# usb_snes_v2.net
KiCad netlist of a schematic drawn in EAGLE
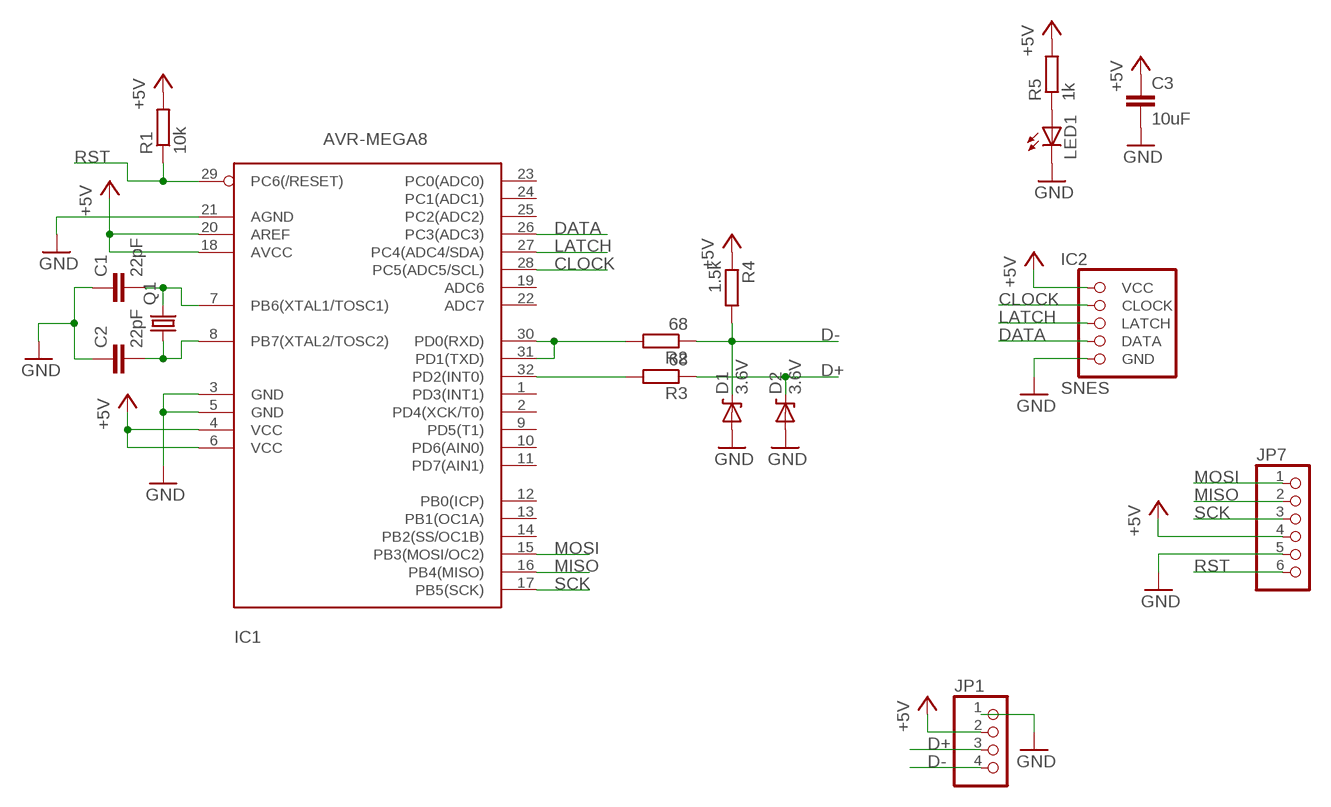
[diagram p0: schematic, sheet 1]

(export (version "E")
  (design (tool "Eeschema 10.0.6"))
  (components
    (comp (ref "C1")
      (value "22pF")
      (footprint "eagle-import:R0805")
      (libsource (lib "eagle-import") (part "C-EUR0805"))
    )
    (comp (ref "C2")
      (value "22pF")
      (footprint "eagle-import:R0805")
      (libsource (lib "eagle-import") (part "C-EUR0805"))
    )
    (comp (ref "C3")
      (value "10uF")
      (footprint "eagle-import:R0805")
      (libsource (lib "eagle-import") (part "C-EUR0805"))
    )
    (comp (ref "D1")
      (value "3.6V")
      (footprint "eagle-import:SOD123FL")
      (libsource (lib "eagle-import") (part "DIODE-ZENERFL"))
    )
    (comp (ref "D2")
      (value "3.6V")
      (footprint "eagle-import:SOD123FL")
      (libsource (lib "eagle-import") (part "DIODE-ZENERFL"))
    )
    (comp (ref "IC1")
      (value "AVR-MEGA8")
      (footprint "eagle-import:TQFP32-08")
      (libsource (lib "eagle-import") (part "AVR-MEGA8-AI"))
    )
    (comp (ref "IC2")
      (value "SNES")
      (footprint "eagle-import:SNES")
      (libsource (lib "eagle-import") (part "SNES"))
    )
    (comp (ref "JP1")
      (value "PINHD-1X4S")
      (footprint "eagle-import:1X04-2MM")
      (libsource (lib "eagle-import") (part "PINHD-1X4S"))
    )
    (comp (ref "JP7")
      (value "PINHD-1X6S")
      (footprint "eagle-import:1X06-2MM")
      (libsource (lib "eagle-import") (part "PINHD-1X6S"))
    )
    (comp (ref "LED1")
      (value "LED0805")
      (footprint "eagle-import:CHIP-LED0805")
      (libsource (lib "eagle-import") (part "LED0805"))
    )
    (comp (ref "Q1")
      (value "CRYSTALHC49UP")
      (footprint "eagle-import:HC49UP")
      (libsource (lib "eagle-import") (part "CRYSTALHC49UP"))
    )
    (comp (ref "R1")
      (value "10k")
      (footprint "eagle-import:R0805")
      (libsource (lib "eagle-import") (part "R-EU_R0805"))
    )
    (comp (ref "R2")
      (value "68")
      (footprint "eagle-import:R0805")
      (libsource (lib "eagle-import") (part "R-EU_R0805"))
    )
    (comp (ref "R3")
      (value "68")
      (footprint "eagle-import:R0805")
      (libsource (lib "eagle-import") (part "R-EU_R0805"))
    )
    (comp (ref "R4")
      (value "1.5k")
      (footprint "eagle-import:R0805")
      (libsource (lib "eagle-import") (part "R-EU_R0805"))
    )
    (comp (ref "R5")
      (value "1k")
      (footprint "eagle-import:R0805")
      (libsource (lib "eagle-import") (part "R-EU_R0805"))
    )
  )
  (nets
    (net (code "1") (name "+5V") (class "Default")
      (node (ref "C3") (pin "1") (pinfunction "1_1") (pintype "passive"))
      (node (ref "IC1") (pin "18") (pinfunction "AVCC_18") (pintype "bidirectional"))
      (node (ref "IC1") (pin "20") (pinfunction "AREF_20") (pintype "bidirectional"))
      (node (ref "IC1") (pin "4") (pinfunction "VCC_4") (pintype "bidirectional"))
      (node (ref "IC1") (pin "6") (pinfunction "VCC_6") (pintype "bidirectional"))
      (node (ref "IC2") (pin "5") (pinfunction "VCC_5") (pintype "passive"))
      (node (ref "JP1") (pin "2") (pinfunction "2_2") (pintype "passive"))
      (node (ref "JP7") (pin "4") (pinfunction "4_4") (pintype "passive"))
      (node (ref "R1") (pin "2") (pinfunction "2_2") (pintype "passive"))
      (node (ref "R4") (pin "1") (pinfunction "1_1") (pintype "passive"))
      (node (ref "R5") (pin "2") (pinfunction "2_2") (pintype "passive"))
    )
    (net (code "2") (name "/CLOCK") (class "Default")
      (node (ref "IC1") (pin "28") (pinfunction "PC5(ADC5/SCL)_28") (pintype "bidirectional"))
      (node (ref "IC2") (pin "4") (pinfunction "CLOCK_4") (pintype "passive"))
    )
    (net (code "3") (name "/D+") (class "Default")
      (node (ref "D2") (pin "C") (pinfunction "C_C") (pintype "passive"))
      (node (ref "JP1") (pin "3") (pinfunction "3_3") (pintype "passive"))
      (node (ref "R3") (pin "1") (pinfunction "1_1") (pintype "passive"))
    )
    (net (code "4") (name "/D-") (class "Default")
      (node (ref "D1") (pin "C") (pinfunction "C_C") (pintype "passive"))
      (node (ref "JP1") (pin "4") (pinfunction "4_4") (pintype "passive"))
      (node (ref "R2") (pin "1") (pinfunction "1_1") (pintype "passive"))
      (node (ref "R4") (pin "2") (pinfunction "2_2") (pintype "passive"))
    )
    (net (code "5") (name "/DATA") (class "Default")
      (node (ref "IC1") (pin "26") (pinfunction "PC3(ADC3)_26") (pintype "bidirectional"))
      (node (ref "IC2") (pin "2") (pinfunction "DATA_2") (pintype "passive"))
    )
    (net (code "6") (name "/LATCH") (class "Default")
      (node (ref "IC1") (pin "27") (pinfunction "PC4(ADC4/SDA)_27") (pintype "bidirectional"))
      (node (ref "IC2") (pin "3") (pinfunction "LATCH_3") (pintype "passive"))
    )
    (net (code "7") (name "/MISO") (class "Default")
      (node (ref "IC1") (pin "16") (pinfunction "PB4(MISO)_16") (pintype "bidirectional"))
      (node (ref "JP7") (pin "2") (pinfunction "2_2") (pintype "passive"))
    )
    (net (code "8") (name "/MOSI") (class "Default")
      (node (ref "IC1") (pin "15") (pinfunction "PB3(MOSI/OC2)_15") (pintype "bidirectional"))
      (node (ref "JP7") (pin "1") (pinfunction "1_1") (pintype "passive"))
    )
    (net (code "9") (name "/RST") (class "Default")
      (node (ref "IC1") (pin "29") (pinfunction "PC6(/RESET)_29") (pintype "bidirectional"))
      (node (ref "JP7") (pin "6") (pinfunction "6_6") (pintype "passive"))
      (node (ref "R1") (pin "1") (pinfunction "1_1") (pintype "passive"))
    )
    (net (code "10") (name "/SCK") (class "Default")
      (node (ref "IC1") (pin "17") (pinfunction "PB5(SCK)_17") (pintype "bidirectional"))
      (node (ref "JP7") (pin "3") (pinfunction "3_3") (pintype "passive"))
    )
    (net (code "11") (name "GND") (class "Default")
      (node (ref "C1") (pin "1") (pinfunction "1_1") (pintype "passive"))
      (node (ref "C2") (pin "1") (pinfunction "1_1") (pintype "passive"))
      (node (ref "C3") (pin "2") (pinfunction "2_2") (pintype "passive"))
      (node (ref "D1") (pin "A") (pinfunction "A_A") (pintype "passive"))
      (node (ref "D2") (pin "A") (pinfunction "A_A") (pintype "passive"))
      (node (ref "IC1") (pin "21") (pinfunction "AGND_21") (pintype "bidirectional"))
      (node (ref "IC1") (pin "3") (pinfunction "GND_3") (pintype "bidirectional"))
      (node (ref "IC1") (pin "5") (pinfunction "GND_5") (pintype "bidirectional"))
      (node (ref "IC2") (pin "1") (pinfunction "GND_1") (pintype "passive"))
      (node (ref "JP1") (pin "1") (pinfunction "1_1") (pintype "passive"))
      (node (ref "JP7") (pin "5") (pinfunction "5_5") (pintype "passive"))
      (node (ref "LED1") (pin "C") (pinfunction "C_C") (pintype "passive"))
    )
    (net (code "12") (name "Net-(IC1-PB6(XTAL1{slash}TOSC1))") (class "Default")
      (node (ref "C1") (pin "2") (pinfunction "2_2") (pintype "passive"))
      (node (ref "IC1") (pin "7") (pinfunction "PB6(XTAL1/TOSC1)_7") (pintype "bidirectional"))
      (node (ref "Q1") (pin "2") (pinfunction "2_2") (pintype "passive"))
    )
    (net (code "13") (name "Net-(IC1-PB7(XTAL2{slash}TOSC2))") (class "Default")
      (node (ref "C2") (pin "2") (pinfunction "2_2") (pintype "passive"))
      (node (ref "IC1") (pin "8") (pinfunction "PB7(XTAL2/TOSC2)_8") (pintype "bidirectional"))
      (node (ref "Q1") (pin "1") (pinfunction "1_1") (pintype "passive"))
    )
    (net (code "14") (name "Net-(IC1-PD0(RXD))") (class "Default")
      (node (ref "IC1") (pin "30") (pinfunction "PD0(RXD)_30") (pintype "bidirectional"))
      (node (ref "IC1") (pin "31") (pinfunction "PD1(TXD)_31") (pintype "bidirectional"))
      (node (ref "R2") (pin "2") (pinfunction "2_2") (pintype "passive"))
    )
    (net (code "15") (name "Net-(IC1-PD2(INT0))") (class "Default")
      (node (ref "IC1") (pin "32") (pinfunction "PD2(INT0)_32") (pintype "bidirectional"))
      (node (ref "R3") (pin "2") (pinfunction "2_2") (pintype "passive"))
    )
    (net (code "16") (name "Net-(LED1-PadA)") (class "Default")
      (node (ref "LED1") (pin "A") (pinfunction "A_A") (pintype "passive"))
      (node (ref "R5") (pin "1") (pinfunction "1_1") (pintype "passive"))
    )
    (net (code "17") (name "unconnected-(IC1-ADC6-Pad19)") (class "Default")
      (node (ref "IC1") (pin "19") (pinfunction "ADC6_19") (pintype "bidirectional"))
    )
    (net (code "18") (name "unconnected-(IC1-ADC7-Pad22)") (class "Default")
      (node (ref "IC1") (pin "22") (pinfunction "ADC7_22") (pintype "bidirectional"))
    )
    (net (code "19") (name "unconnected-(IC1-PB0(ICP)-Pad12)") (class "Default")
      (node (ref "IC1") (pin "12") (pinfunction "PB0(ICP)_12") (pintype "bidirectional"))
    )
    (net (code "20") (name "unconnected-(IC1-PB1(OC1A)-Pad13)") (class "Default")
      (node (ref "IC1") (pin "13") (pinfunction "PB1(OC1A)_13") (pintype "bidirectional"))
    )
    (net (code "21") (name "unconnected-(IC1-PB2(SS{slash}OC1B)-Pad14)") (class "Default")
      (node (ref "IC1") (pin "14") (pinfunction "PB2(SS/OC1B)_14") (pintype "bidirectional"))
    )
    (net (code "22") (name "unconnected-(IC1-PC0(ADC0)-Pad23)") (class "Default")
      (node (ref "IC1") (pin "23") (pinfunction "PC0(ADC0)_23") (pintype "bidirectional"))
    )
    (net (code "23") (name "unconnected-(IC1-PC1(ADC1)-Pad24)") (class "Default")
      (node (ref "IC1") (pin "24") (pinfunction "PC1(ADC1)_24") (pintype "bidirectional"))
    )
    (net (code "24") (name "unconnected-(IC1-PC2(ADC2)-Pad25)") (class "Default")
      (node (ref "IC1") (pin "25") (pinfunction "PC2(ADC2)_25") (pintype "bidirectional"))
    )
    (net (code "25") (name "unconnected-(IC1-PD3(INT1)-Pad1)") (class "Default")
      (node (ref "IC1") (pin "1") (pinfunction "PD3(INT1)_1") (pintype "bidirectional"))
    )
    (net (code "26") (name "unconnected-(IC1-PD4(XCK{slash}T0)-Pad2)") (class "Default")
      (node (ref "IC1") (pin "2") (pinfunction "PD4(XCK/T0)_2") (pintype "bidirectional"))
    )
    (net (code "27") (name "unconnected-(IC1-PD5(T1)-Pad9)") (class "Default")
      (node (ref "IC1") (pin "9") (pinfunction "PD5(T1)_9") (pintype "bidirectional"))
    )
    (net (code "28") (name "unconnected-(IC1-PD6(AIN0)-Pad10)") (class "Default")
      (node (ref "IC1") (pin "10") (pinfunction "PD6(AIN0)_10") (pintype "bidirectional"))
    )
    (net (code "29") (name "unconnected-(IC1-PD7(AIN1)-Pad11)") (class "Default")
      (node (ref "IC1") (pin "11") (pinfunction "PD7(AIN1)_11") (pintype "bidirectional"))
    )
  )
)
